# motor_back.net
KiCad netlist of a schematic drawn in EAGLE
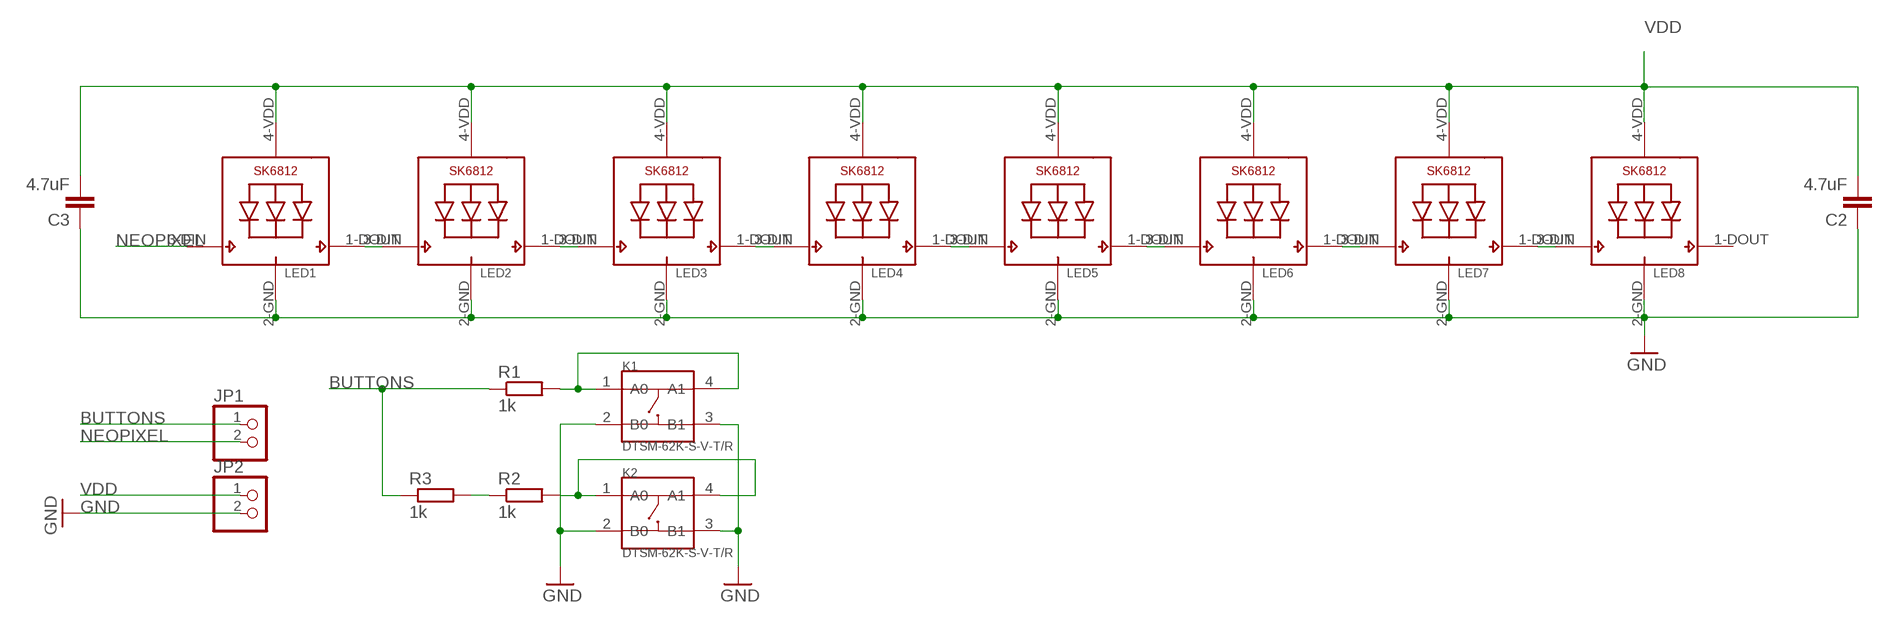
[diagram p0: schematic, sheet 1]

(export (version "E")
  (design (tool "Eeschema 10.0.6"))
  (components
    (comp (ref "C2")
      (value "4.7uF")
      (footprint "eagle-import:C0805")
      (libsource (lib "eagle-import") (part "C-EUC0805"))
    )
    (comp (ref "C3")
      (value "4.7uF")
      (footprint "eagle-import:C0805")
      (libsource (lib "eagle-import") (part "C-EUC0805"))
    )
    (comp (ref "JP1")
      (value "PINHD-1X2")
      (footprint "eagle-import:1X02")
      (libsource (lib "eagle-import") (part "PINHD-1X2"))
    )
    (comp (ref "JP2")
      (value "PINHD-1X2")
      (footprint "eagle-import:1X02")
      (libsource (lib "eagle-import") (part "PINHD-1X2"))
    )
    (comp (ref "K1")
      (value "DTSM-62K-S-V-T/R")
      (footprint "eagle-import:SW4-SMD-6.0X6.0X5.0MM")
      (libsource (lib "eagle-import") (part "SMD-SWITCH-TACTILE-SPST-NO(4P-D6.0MM)"))
    )
    (comp (ref "K2")
      (value "DTSM-62K-S-V-T/R")
      (footprint "eagle-import:SW4-SMD-6.0X6.0X5.0MM")
      (libsource (lib "eagle-import") (part "SMD-SWITCH-TACTILE-SPST-NO(4P-D6.0MM)"))
    )
    (comp (ref "LED1")
      (value "SK6812_3535")
      (footprint "eagle-import:LED3535")
      (libsource (lib "eagle-import") (part "SK6812_3535"))
    )
    (comp (ref "LED2")
      (value "SK6812_3535")
      (footprint "eagle-import:LED3535")
      (libsource (lib "eagle-import") (part "SK6812_3535"))
    )
    (comp (ref "LED3")
      (value "SK6812_3535")
      (footprint "eagle-import:LED3535")
      (libsource (lib "eagle-import") (part "SK6812_3535"))
    )
    (comp (ref "LED4")
      (value "SK6812_3535")
      (footprint "eagle-import:LED3535")
      (libsource (lib "eagle-import") (part "SK6812_3535"))
    )
    (comp (ref "LED5")
      (value "SK6812_3535")
      (footprint "eagle-import:LED3535")
      (libsource (lib "eagle-import") (part "SK6812_3535"))
    )
    (comp (ref "LED6")
      (value "SK6812_3535")
      (footprint "eagle-import:LED3535")
      (libsource (lib "eagle-import") (part "SK6812_3535"))
    )
    (comp (ref "LED7")
      (value "SK6812_3535")
      (footprint "eagle-import:LED3535")
      (libsource (lib "eagle-import") (part "SK6812_3535"))
    )
    (comp (ref "LED8")
      (value "SK6812_3535")
      (footprint "eagle-import:LED3535")
      (libsource (lib "eagle-import") (part "SK6812_3535"))
    )
    (comp (ref "R1")
      (value "1k")
      (footprint "eagle-import:R0603")
      (libsource (lib "eagle-import") (part "R-EU_R0603"))
    )
    (comp (ref "R2")
      (value "1k")
      (footprint "eagle-import:R0603")
      (libsource (lib "eagle-import") (part "R-EU_R0603"))
    )
    (comp (ref "R3")
      (value "1k")
      (footprint "eagle-import:R0603")
      (libsource (lib "eagle-import") (part "R-EU_R0603"))
    )
  )
  (nets
    (net (code "1") (name "/BUTTONS") (class "Default")
      (node (ref "JP1") (pin "1") (pinfunction "1_1") (pintype "passive"))
      (node (ref "R1") (pin "1") (pinfunction "1_1") (pintype "passive"))
      (node (ref "R3") (pin "1") (pinfunction "1_1") (pintype "passive"))
    )
    (net (code "2") (name "/NEOPIXEL") (class "Default")
      (node (ref "JP1") (pin "2") (pinfunction "2_2") (pintype "passive"))
      (node (ref "LED1") (pin "3-DIN") (pinfunction "DI_3-DIN") (pintype "input"))
    )
    (net (code "3") (name "/VDD") (class "Default")
      (node (ref "C2") (pin "2") (pinfunction "2_2") (pintype "passive"))
      (node (ref "C3") (pin "2") (pinfunction "2_2") (pintype "passive"))
      (node (ref "JP2") (pin "1") (pinfunction "1_1") (pintype "passive"))
      (node (ref "LED1") (pin "4-VDD") (pinfunction "VDD_4-VDD") (pintype "power_in"))
      (node (ref "LED2") (pin "4-VDD") (pinfunction "VDD_4-VDD") (pintype "power_in"))
      (node (ref "LED3") (pin "4-VDD") (pinfunction "VDD_4-VDD") (pintype "power_in"))
      (node (ref "LED4") (pin "4-VDD") (pinfunction "VDD_4-VDD") (pintype "power_in"))
      (node (ref "LED5") (pin "4-VDD") (pinfunction "VDD_4-VDD") (pintype "power_in"))
      (node (ref "LED6") (pin "4-VDD") (pinfunction "VDD_4-VDD") (pintype "power_in"))
      (node (ref "LED7") (pin "4-VDD") (pinfunction "VDD_4-VDD") (pintype "power_in"))
      (node (ref "LED8") (pin "4-VDD") (pinfunction "VDD_4-VDD") (pintype "power_in"))
    )
    (net (code "4") (name "GND") (class "Default")
      (node (ref "C2") (pin "1") (pinfunction "1_1") (pintype "passive"))
      (node (ref "C3") (pin "1") (pinfunction "1_1") (pintype "passive"))
      (node (ref "JP2") (pin "2") (pinfunction "2_2") (pintype "passive"))
      (node (ref "K1") (pin "2") (pinfunction "B0_2") (pintype "bidirectional"))
      (node (ref "K1") (pin "3") (pinfunction "B1_3") (pintype "bidirectional"))
      (node (ref "K2") (pin "2") (pinfunction "B0_2") (pintype "bidirectional"))
      (node (ref "K2") (pin "3") (pinfunction "B1_3") (pintype "bidirectional"))
      (node (ref "LED1") (pin "2-GND") (pinfunction "GND_2-GND") (pintype "power_in"))
      (node (ref "LED2") (pin "2-GND") (pinfunction "GND_2-GND") (pintype "power_in"))
      (node (ref "LED3") (pin "2-GND") (pinfunction "GND_2-GND") (pintype "power_in"))
      (node (ref "LED4") (pin "2-GND") (pinfunction "GND_2-GND") (pintype "power_in"))
      (node (ref "LED5") (pin "2-GND") (pinfunction "GND_2-GND") (pintype "power_in"))
      (node (ref "LED6") (pin "2-GND") (pinfunction "GND_2-GND") (pintype "power_in"))
      (node (ref "LED7") (pin "2-GND") (pinfunction "GND_2-GND") (pintype "power_in"))
      (node (ref "LED8") (pin "2-GND") (pinfunction "GND_2-GND") (pintype "power_in"))
    )
    (net (code "5") (name "Net-(K1-A0)") (class "Default")
      (node (ref "K1") (pin "1") (pinfunction "A0_1") (pintype "bidirectional"))
      (node (ref "K1") (pin "4") (pinfunction "A1_4") (pintype "bidirectional"))
      (node (ref "R1") (pin "2") (pinfunction "2_2") (pintype "passive"))
    )
    (net (code "6") (name "Net-(K2-A0)") (class "Default")
      (node (ref "K2") (pin "1") (pinfunction "A0_1") (pintype "bidirectional"))
      (node (ref "K2") (pin "4") (pinfunction "A1_4") (pintype "bidirectional"))
      (node (ref "R2") (pin "2") (pinfunction "2_2") (pintype "passive"))
    )
    (net (code "7") (name "Net-(LED1-DO)") (class "Default")
      (node (ref "LED1") (pin "1-DOUT") (pinfunction "DO_1-DOUT") (pintype "output"))
      (node (ref "LED2") (pin "3-DIN") (pinfunction "DI_3-DIN") (pintype "input"))
    )
    (net (code "8") (name "Net-(LED2-DO)") (class "Default")
      (node (ref "LED2") (pin "1-DOUT") (pinfunction "DO_1-DOUT") (pintype "output"))
      (node (ref "LED3") (pin "3-DIN") (pinfunction "DI_3-DIN") (pintype "input"))
    )
    (net (code "9") (name "Net-(LED3-DO)") (class "Default")
      (node (ref "LED3") (pin "1-DOUT") (pinfunction "DO_1-DOUT") (pintype "output"))
      (node (ref "LED4") (pin "3-DIN") (pinfunction "DI_3-DIN") (pintype "input"))
    )
    (net (code "10") (name "Net-(LED4-DO)") (class "Default")
      (node (ref "LED4") (pin "1-DOUT") (pinfunction "DO_1-DOUT") (pintype "output"))
      (node (ref "LED5") (pin "3-DIN") (pinfunction "DI_3-DIN") (pintype "input"))
    )
    (net (code "11") (name "Net-(LED5-DO)") (class "Default")
      (node (ref "LED5") (pin "1-DOUT") (pinfunction "DO_1-DOUT") (pintype "output"))
      (node (ref "LED6") (pin "3-DIN") (pinfunction "DI_3-DIN") (pintype "input"))
    )
    (net (code "12") (name "Net-(LED6-DO)") (class "Default")
      (node (ref "LED6") (pin "1-DOUT") (pinfunction "DO_1-DOUT") (pintype "output"))
      (node (ref "LED7") (pin "3-DIN") (pinfunction "DI_3-DIN") (pintype "input"))
    )
    (net (code "13") (name "Net-(LED7-DO)") (class "Default")
      (node (ref "LED7") (pin "1-DOUT") (pinfunction "DO_1-DOUT") (pintype "output"))
      (node (ref "LED8") (pin "3-DIN") (pinfunction "DI_3-DIN") (pintype "input"))
    )
    (net (code "14") (name "Net-(R2-Pad1)") (class "Default")
      (node (ref "R2") (pin "1") (pinfunction "1_1") (pintype "passive"))
      (node (ref "R3") (pin "2") (pinfunction "2_2") (pintype "passive"))
    )
    (net (code "15") (name "unconnected-(LED8-DO-Pad1-DOUT)") (class "Default")
      (node (ref "LED8") (pin "1-DOUT") (pinfunction "DO_1-DOUT") (pintype "output"))
    )
  )
)
